# SunS_MCU.net
KiCad netlist of a schematic drawn in Altium Designer
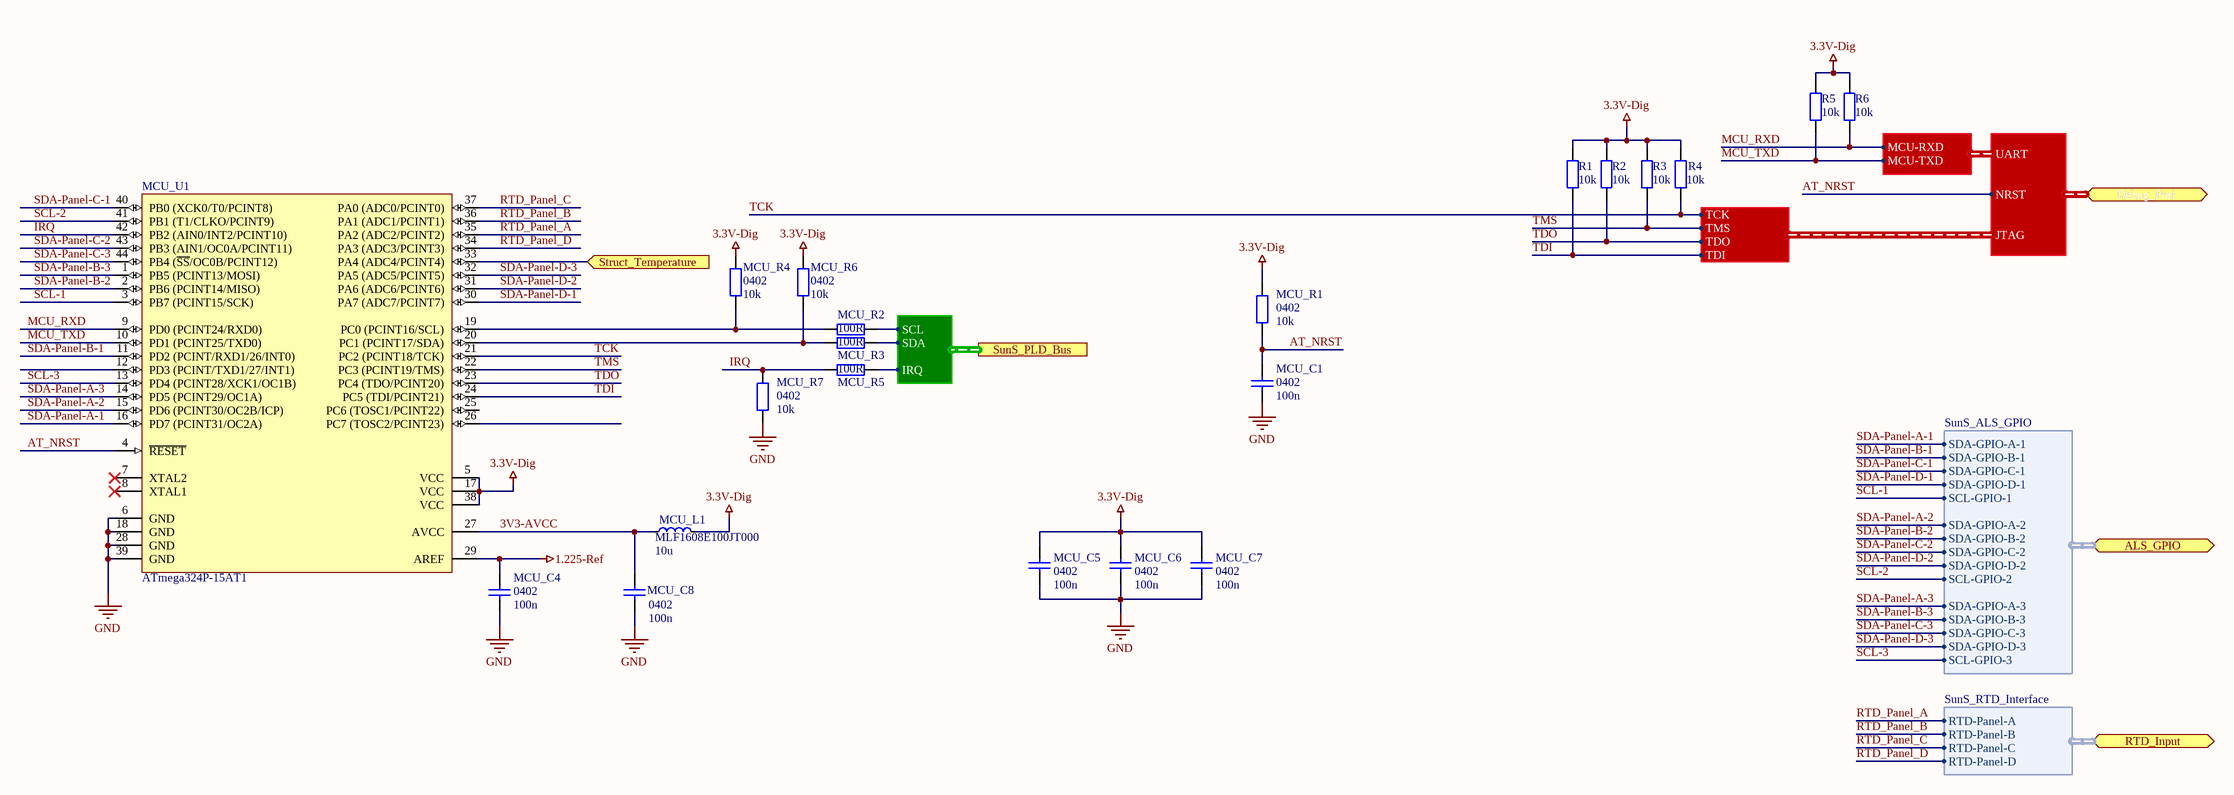
[diagram p0: SunS_MCU.SchDoc]

(export (version "E")
  (design (tool "Eeschema 10.0.6"))
  (components
    (comp (ref "MCU_C1")
      (value "0402")
      (footprint "SMD_Capacitor_0402")
      (description "Capacitor")
      (fields (field (name "ALTIUM_VALUE") "100n") (field (name "PUBLISHER") "Altium Limited"))
      (libsource (lib "Miscellaneous Devices") (part "Cap"))
    )
    (comp (ref "MCU_C4")
      (value "0402")
      (footprint "SMD_Capacitor_0402")
      (description "Capacitor")
      (fields (field (name "ALTIUM_VALUE") "100n") (field (name "PUBLISHER") "Altium Limited"))
      (libsource (lib "Miscellaneous Devices") (part "Cap"))
    )
    (comp (ref "MCU_C5")
      (value "0402")
      (footprint "SMD_Capacitor_0402")
      (description "Capacitor")
      (fields (field (name "ALTIUM_VALUE") "100n") (field (name "PUBLISHER") "Altium Limited"))
      (libsource (lib "Miscellaneous Devices") (part "Cap"))
    )
    (comp (ref "MCU_C6")
      (value "0402")
      (footprint "SMD_Capacitor_0402")
      (description "Capacitor")
      (fields (field (name "ALTIUM_VALUE") "100n") (field (name "PUBLISHER") "Altium Limited"))
      (libsource (lib "Miscellaneous Devices") (part "Cap"))
    )
    (comp (ref "MCU_C7")
      (value "0402")
      (footprint "SMD_Capacitor_0402")
      (description "Capacitor")
      (fields (field (name "ALTIUM_VALUE") "100n") (field (name "PUBLISHER") "Altium Limited"))
      (libsource (lib "Miscellaneous Devices") (part "Cap"))
    )
    (comp (ref "MCU_C8")
      (value "0402")
      (footprint "SMD_Capacitor_0402")
      (description "Capacitor")
      (fields (field (name "ALTIUM_VALUE") "100n") (field (name "PUBLISHER") "Altium Limited"))
      (libsource (lib "Miscellaneous Devices") (part "Cap"))
    )
    (comp (ref "MCU_L1")
      (value "10u")
      (footprint "0603")
      (description "Generic Inductor")
      (fields
        (field (name "MANUFACTURER") "TDK")
        (field (name "MANUFACTURER PART NUMBER") "MLF1608E100JT000")
      )
      (libsource (lib "inductors") (part "Inductor"))
    )
    (comp (ref "MCU_R1")
      (value "0402")
      (footprint "SMD_Capacitor_0402")
      (description "Resistor")
      (fields (field (name "ALTIUM_VALUE") "10k") (field (name "PUBLISHER") "Altium Limited"))
      (libsource (lib "Miscellaneous Devices") (part "Res2"))
    )
    (comp (ref "MCU_R2")
      (value "100R")
      (footprint "SMD_Resistor_0402")
      (description "100R/1% Vishay CRCW 0402 Resistor. 63mW, 100ppm, 50V.")
      (fields
        (field (name "MANUFACTURER") "Vishay")
        (field (name "MANUFACTURERPARTNUMBER") "CRCW0402100RFKxxxx")
      )
      (libsource (lib "resistors") (part "CRCW0402100RFKxxxx"))
    )
    (comp (ref "MCU_R3")
      (value "100R")
      (footprint "SMD_Resistor_0402")
      (description "100R/1% Vishay CRCW 0402 Resistor. 63mW, 100ppm, 50V.")
      (fields
        (field (name "MANUFACTURER") "Vishay")
        (field (name "MANUFACTURERPARTNUMBER") "CRCW0402100RFKxxxx")
      )
      (libsource (lib "resistors") (part "CRCW0402100RFKxxxx"))
    )
    (comp (ref "MCU_R4")
      (value "0402")
      (footprint "SMD_Capacitor_0402")
      (description "Resistor")
      (fields (field (name "ALTIUM_VALUE") "10k") (field (name "PUBLISHER") "Altium Limited"))
      (libsource (lib "Miscellaneous Devices") (part "Res2"))
    )
    (comp (ref "MCU_R5")
      (value "100R")
      (footprint "SMD_Resistor_0402")
      (description "100R/1% Vishay CRCW 0402 Resistor. 63mW, 100ppm, 50V.")
      (fields
        (field (name "MANUFACTURER") "Vishay")
        (field (name "MANUFACTURERPARTNUMBER") "CRCW0402100RFKxxxx")
      )
      (libsource (lib "resistors") (part "CRCW0402100RFKxxxx"))
    )
    (comp (ref "MCU_R6")
      (value "0402")
      (footprint "SMD_Capacitor_0402")
      (description "Resistor")
      (fields (field (name "ALTIUM_VALUE") "10k") (field (name "PUBLISHER") "Altium Limited"))
      (libsource (lib "Miscellaneous Devices") (part "Res2"))
    )
    (comp (ref "MCU_R7")
      (value "0402")
      (footprint "SMD_Capacitor_0402")
      (description "Resistor")
      (fields (field (name "ALTIUM_VALUE") "10k") (field (name "PUBLISHER") "Altium Limited"))
      (libsource (lib "Miscellaneous Devices") (part "Res2"))
    )
    (comp (ref "MCU_U1")
      (value "ATmega324P-15AT1")
      (footprint "TQFP-44")
      (libsource (lib "microcircuits") (part "ATmega324P-15AT1"))
    )
    (comp (ref "R1") (value "10k") (footprint "SMD_Resistor_0402") (libsource (lib "resistors") (part "Res")))
    (comp (ref "R2") (value "10k") (footprint "SMD_Resistor_0402") (libsource (lib "resistors") (part "Res")))
    (comp (ref "R3") (value "10k") (footprint "SMD_Resistor_0402") (libsource (lib "resistors") (part "Res")))
    (comp (ref "R4") (value "10k") (footprint "SMD_Resistor_0402") (libsource (lib "resistors") (part "Res")))
    (comp (ref "R5") (value "10k") (footprint "SMD_Resistor_0402") (libsource (lib "resistors") (part "Res")))
    (comp (ref "R6") (value "10k") (footprint "SMD_Resistor_0402") (libsource (lib "resistors") (part "Res")))
  )
  (nets
    (net (code "7") (name "/3V3-AVCC") (class "Default")
      (node (ref "MCU_C8") (pin "2") (pinfunction "2_2") (pintype "passive"))
      (node (ref "MCU_L1") (pin "1") (pinfunction "1_1") (pintype "passive"))
      (node (ref "MCU_U1") (pin "27") (pinfunction "AVCC_27") (pintype "power_in"))
    )
    (net (code "8") (name "/AT_NRST") (class "Default")
      (node (ref "MCU_C1") (pin "2") (pinfunction "2_2") (pintype "passive"))
      (node (ref "MCU_R1") (pin "1") (pinfunction "1_1") (pintype "passive"))
      (node (ref "MCU_U1") (pin "4") (pinfunction "~{RESET}_4") (pintype "input"))
    )
    (net (code "10") (name "/IRQ") (class "Default")
      (node (ref "MCU_R5") (pin "1") (pinfunction "1_1") (pintype "passive"))
      (node (ref "MCU_R7") (pin "2") (pinfunction "2_2") (pintype "passive"))
      (node (ref "MCU_U1") (pin "42") (pinfunction "PB2_(AIN0/INT2/PCINT10)_42") (pintype "bidirectional"))
    )
    (net (code "11") (name "/MCU_RXD") (class "Default")
      (node (ref "MCU_U1") (pin "9") (pinfunction "PD0_(PCINT24/RXD0)_9") (pintype "bidirectional"))
      (node (ref "R6") (pin "2") (pinfunction "2_2") (pintype "passive"))
    )
    (net (code "12") (name "/MCU_TXD") (class "Default")
      (node (ref "MCU_U1") (pin "10") (pinfunction "PD1_(PCINT25/TXD0)_10") (pintype "bidirectional"))
      (node (ref "R5") (pin "2") (pinfunction "2_2") (pintype "passive"))
    )
    (net (code "13") (name "/RTD_Panel_A") (class "Default")
      (node (ref "MCU_U1") (pin "35") (pinfunction "PA2_(ADC2/PCINT2)_35") (pintype "bidirectional"))
    )
    (net (code "14") (name "/RTD_Panel_B") (class "Default")
      (node (ref "MCU_U1") (pin "36") (pinfunction "PA1_(ADC1/PCINT1)_36") (pintype "bidirectional"))
    )
    (net (code "15") (name "/RTD_Panel_C") (class "Default")
      (node (ref "MCU_U1") (pin "37") (pinfunction "PA0_(ADC0/PCINT0)_37") (pintype "bidirectional"))
    )
    (net (code "16") (name "/RTD_Panel_D") (class "Default")
      (node (ref "MCU_U1") (pin "34") (pinfunction "PA3_(ADC3/PCINT3)_34") (pintype "bidirectional"))
    )
    (net (code "17") (name "/SCL") (class "Default")
      (node (ref "MCU_R2") (pin "2") (pinfunction "2_2") (pintype "passive"))
    )
    (net (code "18") (name "/SCL-1") (class "Default")
      (node (ref "MCU_U1") (pin "3") (pinfunction "PB7_(PCINT15/SCK)_3") (pintype "bidirectional"))
    )
    (net (code "19") (name "/SCL-2") (class "Default")
      (node (ref "MCU_U1") (pin "41") (pinfunction "PB1_(T1/CLKO/PCINT9)_41") (pintype "bidirectional"))
    )
    (net (code "20") (name "/SCL-3") (class "Default")
      (node (ref "MCU_U1") (pin "13") (pinfunction "PD4_(PCINT28/XCK1/OC1B)_13") (pintype "bidirectional"))
    )
    (net (code "21") (name "/SDA") (class "Default")
      (node (ref "MCU_R3") (pin "2") (pinfunction "2_2") (pintype "passive"))
    )
    (net (code "22") (name "/SDA-Panel-A-1") (class "Default")
      (node (ref "MCU_U1") (pin "16") (pinfunction "PD7_(PCINT31/OC2A)_16") (pintype "bidirectional"))
    )
    (net (code "23") (name "/SDA-Panel-A-2") (class "Default")
      (node (ref "MCU_U1") (pin "15") (pinfunction "PD6_(PCINT30/OC2B/ICP)_15") (pintype "bidirectional"))
    )
    (net (code "24") (name "/SDA-Panel-A-3") (class "Default")
      (node (ref "MCU_U1") (pin "14") (pinfunction "PD5_(PCINT29/OC1A)_14") (pintype "bidirectional"))
    )
    (net (code "25") (name "/SDA-Panel-B-1") (class "Default")
      (node (ref "MCU_U1") (pin "11") (pinfunction "PD2_(PCINT/RXD1/26/INT0)_11") (pintype "bidirectional"))
    )
    (net (code "26") (name "/SDA-Panel-B-2") (class "Default")
      (node (ref "MCU_U1") (pin "2") (pinfunction "PB6_(PCINT14/MISO)_2") (pintype "bidirectional"))
    )
    (net (code "27") (name "/SDA-Panel-B-3") (class "Default")
      (node (ref "MCU_U1") (pin "1") (pinfunction "PB5_(PCINT13/MOSI)_1") (pintype "bidirectional"))
    )
    (net (code "28") (name "/SDA-Panel-C-1") (class "Default")
      (node (ref "MCU_U1") (pin "40") (pinfunction "PB0_(XCK0/T0/PCINT8)_40") (pintype "bidirectional"))
    )
    (net (code "29") (name "/SDA-Panel-C-2") (class "Default")
      (node (ref "MCU_U1") (pin "43") (pinfunction "PB3_(AIN1/OC0A/PCINT11)_43") (pintype "bidirectional"))
    )
    (net (code "30") (name "/SDA-Panel-C-3") (class "Default")
      (node (ref "MCU_U1") (pin "44") (pinfunction "PB4_(~{SS}/OC0B/PCINT12)_44") (pintype "bidirectional"))
    )
    (net (code "31") (name "/SDA-Panel-D-1") (class "Default")
      (node (ref "MCU_U1") (pin "30") (pinfunction "PA7_(ADC7/PCINT7)_30") (pintype "bidirectional"))
    )
    (net (code "32") (name "/SDA-Panel-D-2") (class "Default")
      (node (ref "MCU_U1") (pin "31") (pinfunction "PA6_(ADC6/PCINT6)_31") (pintype "bidirectional"))
    )
    (net (code "33") (name "/SDA-Panel-D-3") (class "Default")
      (node (ref "MCU_U1") (pin "32") (pinfunction "PA5_(ADC5/PCINT5)_32") (pintype "bidirectional"))
    )
    (net (code "34") (name "/Struct_Temperature") (class "Default")
      (node (ref "MCU_U1") (pin "33") (pinfunction "PA4_(ADC4/PCINT4)_33") (pintype "bidirectional"))
    )
    (net (code "35") (name "/TCK") (class "Default")
      (node (ref "MCU_U1") (pin "21") (pinfunction "PC2_(PCINT18/TCK)_21") (pintype "bidirectional"))
      (node (ref "R4") (pin "2") (pinfunction "2_2") (pintype "passive"))
    )
    (net (code "36") (name "/TDI") (class "Default")
      (node (ref "MCU_U1") (pin "24") (pinfunction "PC5_(TDI/PCINT21)_24") (pintype "bidirectional"))
      (node (ref "R1") (pin "2") (pinfunction "2_2") (pintype "passive"))
    )
    (net (code "37") (name "/TDO") (class "Default")
      (node (ref "MCU_U1") (pin "23") (pinfunction "PC4_(TDO/PCINT20)_23") (pintype "bidirectional"))
      (node (ref "R2") (pin "2") (pinfunction "2_2") (pintype "passive"))
    )
    (net (code "38") (name "/TMS") (class "Default")
      (node (ref "MCU_U1") (pin "22") (pinfunction "PC3_(PCINT19/TMS)_22") (pintype "bidirectional"))
      (node (ref "R3") (pin "2") (pinfunction "2_2") (pintype "passive"))
    )
    (net (code "44") (name "1.225-Ref") (class "Default")
      (node (ref "MCU_C4") (pin "2") (pinfunction "2_2") (pintype "passive"))
      (node (ref "MCU_U1") (pin "29") (pinfunction "AREF_29") (pintype "power_in"))
    )
    (net (code "45") (name "3.3V-Dig") (class "Default")
      (node (ref "MCU_C5") (pin "2") (pinfunction "2_2") (pintype "passive"))
      (node (ref "MCU_C6") (pin "2") (pinfunction "2_2") (pintype "passive"))
      (node (ref "MCU_C7") (pin "2") (pinfunction "2_2") (pintype "passive"))
      (node (ref "MCU_L1") (pin "2") (pinfunction "2_2") (pintype "passive"))
      (node (ref "MCU_R1") (pin "2") (pinfunction "2_2") (pintype "passive"))
      (node (ref "MCU_R4") (pin "2") (pinfunction "2_2") (pintype "passive"))
      (node (ref "MCU_R6") (pin "2") (pinfunction "2_2") (pintype "passive"))
      (node (ref "MCU_U1") (pin "17") (pinfunction "VCC_17") (pintype "power_in"))
      (node (ref "MCU_U1") (pin "38") (pinfunction "VCC_38") (pintype "power_in"))
      (node (ref "MCU_U1") (pin "5") (pinfunction "VCC_5") (pintype "power_in"))
      (node (ref "R1") (pin "1") (pinfunction "1_1") (pintype "passive"))
      (node (ref "R2") (pin "1") (pinfunction "1_1") (pintype "passive"))
      (node (ref "R3") (pin "1") (pinfunction "1_1") (pintype "passive"))
      (node (ref "R4") (pin "1") (pinfunction "1_1") (pintype "passive"))
      (node (ref "R5") (pin "1") (pinfunction "1_1") (pintype "passive"))
      (node (ref "R6") (pin "1") (pinfunction "1_1") (pintype "passive"))
    )
    (net (code "46") (name "GND") (class "Default")
      (node (ref "MCU_C1") (pin "1") (pinfunction "1_1") (pintype "passive"))
      (node (ref "MCU_C4") (pin "1") (pinfunction "1_1") (pintype "passive"))
      (node (ref "MCU_C5") (pin "1") (pinfunction "1_1") (pintype "passive"))
      (node (ref "MCU_C6") (pin "1") (pinfunction "1_1") (pintype "passive"))
      (node (ref "MCU_C7") (pin "1") (pinfunction "1_1") (pintype "passive"))
      (node (ref "MCU_C8") (pin "1") (pinfunction "1_1") (pintype "passive"))
      (node (ref "MCU_R7") (pin "1") (pinfunction "1_1") (pintype "passive"))
      (node (ref "MCU_U1") (pin "18") (pinfunction "GND_18") (pintype "power_in"))
      (node (ref "MCU_U1") (pin "28") (pinfunction "GND_28") (pintype "power_in"))
      (node (ref "MCU_U1") (pin "39") (pinfunction "GND_39") (pintype "power_in"))
      (node (ref "MCU_U1") (pin "6") (pinfunction "GND_6") (pintype "power_in"))
    )
    (net (code "47") (name "Net-(MCU_U1-PC0_(PCINT16{slash}SCL))") (class "Default")
      (node (ref "MCU_R2") (pin "1") (pinfunction "1_1") (pintype "passive"))
      (node (ref "MCU_R4") (pin "1") (pinfunction "1_1") (pintype "passive"))
      (node (ref "MCU_U1") (pin "19") (pinfunction "PC0_(PCINT16/SCL)_19") (pintype "bidirectional"))
    )
    (net (code "48") (name "Net-(MCU_U1-PC1_(PCINT17{slash}SDA))") (class "Default")
      (node (ref "MCU_R3") (pin "1") (pinfunction "1_1") (pintype "passive"))
      (node (ref "MCU_R6") (pin "1") (pinfunction "1_1") (pintype "passive"))
      (node (ref "MCU_U1") (pin "20") (pinfunction "PC1_(PCINT17/SDA)_20") (pintype "bidirectional"))
    )
    (net (code "49") (name "unconnected-(MCU_R5-Pad2)") (class "Default")
      (node (ref "MCU_R5") (pin "2") (pinfunction "2_2") (pintype "passive"))
    )
    (net (code "50") (name "unconnected-(MCU_U1-PC6_(TOSC1{slash}PCINT22)-Pad25)") (class "Default")
      (node (ref "MCU_U1") (pin "25") (pinfunction "PC6_(TOSC1/PCINT22)_25") (pintype "bidirectional"))
    )
    (net (code "51") (name "unconnected-(MCU_U1-PC7_(TOSC2{slash}PCINT23)-Pad26)") (class "Default")
      (node (ref "MCU_U1") (pin "26") (pinfunction "PC7_(TOSC2/PCINT23)_26") (pintype "bidirectional"))
    )
    (net (code "52") (name "unconnected-(MCU_U1-PD3_(PCINT{slash}TXD1{slash}27{slash}INT1)-Pad12)") (class "Default")
      (node (ref "MCU_U1") (pin "12") (pinfunction "PD3_(PCINT/TXD1/27/INT1)_12") (pintype "bidirectional"))
    )
    (net (code "53") (name "unconnected-(MCU_U1-XTAL1-Pad8)") (class "Default")
      (node (ref "MCU_U1") (pin "8") (pinfunction "XTAL1_8") (pintype "passive+no_connect"))
    )
    (net (code "54") (name "unconnected-(MCU_U1-XTAL2-Pad7)") (class "Default")
      (node (ref "MCU_U1") (pin "7") (pinfunction "XTAL2_7") (pintype "passive+no_connect"))
    )
  )
)
